# Quadrotor.net
KiCad netlist of a schematic drawn in Altium Designer
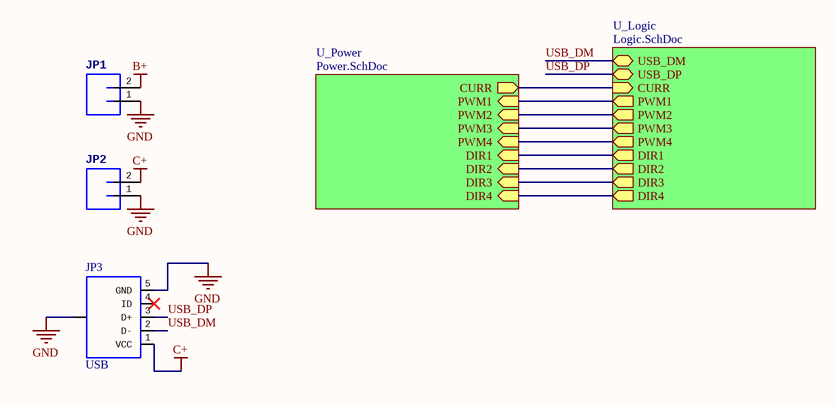
[diagram p0: Quadrotor.SchDoc]

(export (version "E")
  (design (tool "Eeschema 10.0.6"))
  (components
    (comp (ref "JP1")
      (value "~")
      (footprint "JST-2-PTH-VERT")
      (libsource (lib "Components") (part "JST_2_RIGHT"))
    )
    (comp (ref "JP2")
      (value "~")
      (footprint "JST-2-PTH-VERT")
      (libsource (lib "Components") (part "JST_2_RIGHT"))
    )
    (comp (ref "JP3")
      (value "USB")
      (footprint "USB-MICROB")
      (libsource (lib "Components") (part "USB_MICROB_PLUG-SMT"))
    )
  )
  (nets
    (net (code "10") (name "/USB_DM") (class "Default")
      (node (ref "JP3") (pin "2") (pinfunction "D-_2") (pintype "passive"))
    )
    (net (code "11") (name "/USB_DP") (class "Default")
      (node (ref "JP3") (pin "3") (pinfunction "D+_3") (pintype "passive"))
    )
    (net (code "12") (name "B+") (class "Default")
      (node (ref "JP1") (pin "2") (pinfunction "2_2") (pintype "passive"))
    )
    (net (code "13") (name "C+") (class "Default")
      (node (ref "JP2") (pin "2") (pinfunction "2_2") (pintype "passive"))
      (node (ref "JP3") (pin "1") (pinfunction "VCC_1") (pintype "passive"))
    )
    (net (code "14") (name "GND") (class "Default")
      (node (ref "JP1") (pin "1") (pinfunction "1_1") (pintype "passive"))
      (node (ref "JP2") (pin "1") (pinfunction "1_1") (pintype "passive"))
      (node (ref "JP3") (pin "5") (pinfunction "GND_5") (pintype "passive"))
      (node (ref "JP3") (pin "6") (pinfunction "SHIELD_6") (pintype "passive"))
    )
    (net (code "15") (name "unconnected-(JP3-ID-Pad4)") (class "Default")
      (node (ref "JP3") (pin "4") (pinfunction "ID_4") (pintype "passive+no_connect"))
    )
  )
)
